# 07_CONNECTORS.net
KiCad netlist of a schematic drawn in Altium Designer
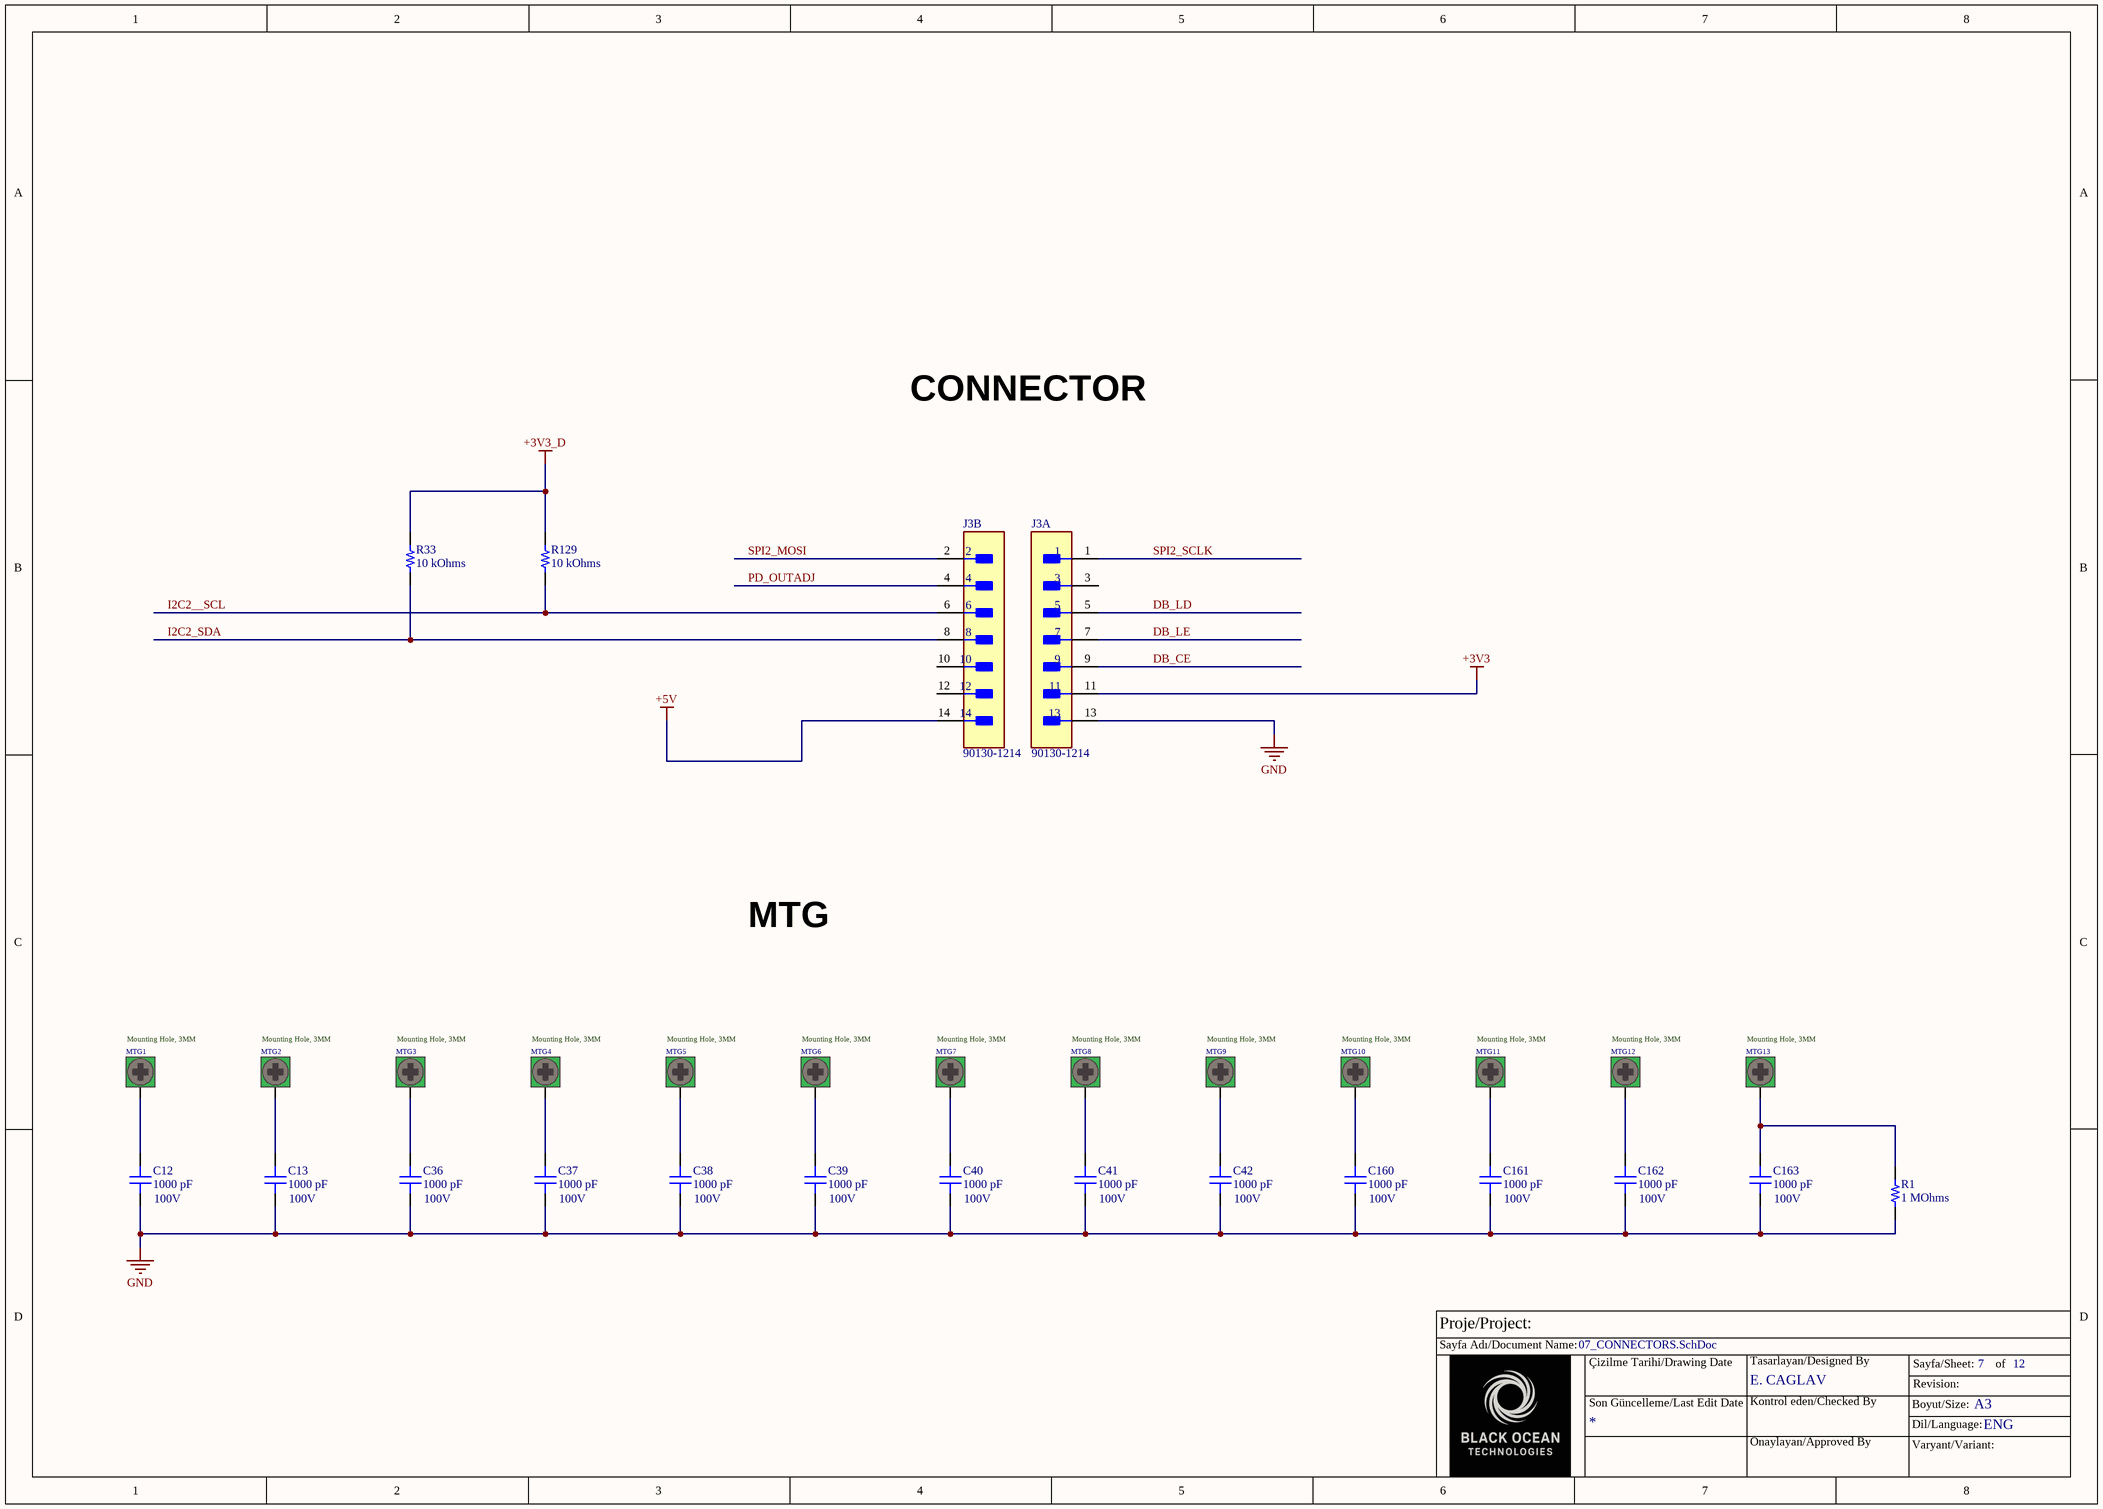
[diagram p0: 07_CONNECTORS.SchDoc]

(export (version "E")
  (design (tool "Eeschema 10.0.6"))
  (components
    (comp (ref "C12")
      (value "1000 pF")
      (footprint "CAP 0402_1005")
      (description "CAP CER 1000PF 100V C0G/NP0 0402")
      (fields
        (field (name "PART NUMBER") "C0402H102J1GAC7867")
        (field (name "CAPACITANCE") "1000 pF")
        (field (name "MANUFACTURER") "KEMET")
        (field (name "VOLTAGE - RATED") "100V")
      )
      (libsource (lib "Celestial Altium Library - altium_library") (part "Capacitor"))
    )
    (comp (ref "C13")
      (value "1000 pF")
      (footprint "CAP 0402_1005")
      (description "CAP CER 1000PF 100V C0G/NP0 0402")
      (fields
        (field (name "PART NUMBER") "C0402H102J1GAC7867")
        (field (name "CAPACITANCE") "1000 pF")
        (field (name "MANUFACTURER") "KEMET")
        (field (name "VOLTAGE - RATED") "100V")
      )
      (libsource (lib "Celestial Altium Library - altium_library") (part "Capacitor"))
    )
    (comp (ref "C36")
      (value "1000 pF")
      (footprint "CAP 0402_1005")
      (description "CAP CER 1000PF 100V C0G/NP0 0402")
      (fields
        (field (name "PART NUMBER") "C0402H102J1GAC7867")
        (field (name "CAPACITANCE") "1000 pF")
        (field (name "MANUFACTURER") "KEMET")
        (field (name "VOLTAGE - RATED") "100V")
      )
      (libsource (lib "Celestial Altium Library - altium_library") (part "Capacitor"))
    )
    (comp (ref "C37")
      (value "1000 pF")
      (footprint "CAP 0402_1005")
      (description "CAP CER 1000PF 100V C0G/NP0 0402")
      (fields
        (field (name "PART NUMBER") "C0402H102J1GAC7867")
        (field (name "CAPACITANCE") "1000 pF")
        (field (name "MANUFACTURER") "KEMET")
        (field (name "VOLTAGE - RATED") "100V")
      )
      (libsource (lib "Celestial Altium Library - altium_library") (part "Capacitor"))
    )
    (comp (ref "C38")
      (value "1000 pF")
      (footprint "CAP 0402_1005")
      (description "CAP CER 1000PF 100V C0G/NP0 0402")
      (fields
        (field (name "PART NUMBER") "C0402H102J1GAC7867")
        (field (name "CAPACITANCE") "1000 pF")
        (field (name "MANUFACTURER") "KEMET")
        (field (name "VOLTAGE - RATED") "100V")
      )
      (libsource (lib "Celestial Altium Library - altium_library") (part "Capacitor"))
    )
    (comp (ref "C39")
      (value "1000 pF")
      (footprint "CAP 0402_1005")
      (description "CAP CER 1000PF 100V C0G/NP0 0402")
      (fields
        (field (name "PART NUMBER") "C0402H102J1GAC7867")
        (field (name "CAPACITANCE") "1000 pF")
        (field (name "MANUFACTURER") "KEMET")
        (field (name "VOLTAGE - RATED") "100V")
      )
      (libsource (lib "Celestial Altium Library - altium_library") (part "Capacitor"))
    )
    (comp (ref "C40")
      (value "1000 pF")
      (footprint "CAP 0402_1005")
      (description "CAP CER 1000PF 100V C0G/NP0 0402")
      (fields
        (field (name "PART NUMBER") "C0402H102J1GAC7867")
        (field (name "CAPACITANCE") "1000 pF")
        (field (name "MANUFACTURER") "KEMET")
        (field (name "VOLTAGE - RATED") "100V")
      )
      (libsource (lib "Celestial Altium Library - altium_library") (part "Capacitor"))
    )
    (comp (ref "C41")
      (value "1000 pF")
      (footprint "CAP 0402_1005")
      (description "CAP CER 1000PF 100V C0G/NP0 0402")
      (fields
        (field (name "PART NUMBER") "C0402H102J1GAC7867")
        (field (name "CAPACITANCE") "1000 pF")
        (field (name "MANUFACTURER") "KEMET")
        (field (name "VOLTAGE - RATED") "100V")
      )
      (libsource (lib "Celestial Altium Library - altium_library") (part "Capacitor"))
    )
    (comp (ref "C42")
      (value "1000 pF")
      (footprint "CAP 0402_1005")
      (description "CAP CER 1000PF 100V C0G/NP0 0402")
      (fields
        (field (name "PART NUMBER") "C0402H102J1GAC7867")
        (field (name "CAPACITANCE") "1000 pF")
        (field (name "MANUFACTURER") "KEMET")
        (field (name "VOLTAGE - RATED") "100V")
      )
      (libsource (lib "Celestial Altium Library - altium_library") (part "Capacitor"))
    )
    (comp (ref "C160")
      (value "1000 pF")
      (footprint "CAP 0402_1005")
      (description "CAP CER 1000PF 100V C0G/NP0 0402")
      (fields
        (field (name "PART NUMBER") "C0402H102J1GAC7867")
        (field (name "CAPACITANCE") "1000 pF")
        (field (name "MANUFACTURER") "KEMET")
        (field (name "VOLTAGE - RATED") "100V")
      )
      (libsource (lib "Celestial Altium Library - altium_library") (part "Capacitor"))
    )
    (comp (ref "C161")
      (value "1000 pF")
      (footprint "CAP 0402_1005")
      (description "CAP CER 1000PF 100V C0G/NP0 0402")
      (fields
        (field (name "PART NUMBER") "C0402H102J1GAC7867")
        (field (name "CAPACITANCE") "1000 pF")
        (field (name "MANUFACTURER") "KEMET")
        (field (name "VOLTAGE - RATED") "100V")
      )
      (libsource (lib "Celestial Altium Library - altium_library") (part "Capacitor"))
    )
    (comp (ref "C162")
      (value "1000 pF")
      (footprint "CAP 0402_1005")
      (description "CAP CER 1000PF 100V C0G/NP0 0402")
      (fields
        (field (name "PART NUMBER") "C0402H102J1GAC7867")
        (field (name "CAPACITANCE") "1000 pF")
        (field (name "MANUFACTURER") "KEMET")
        (field (name "VOLTAGE - RATED") "100V")
      )
      (libsource (lib "Celestial Altium Library - altium_library") (part "Capacitor"))
    )
    (comp (ref "C163")
      (value "1000 pF")
      (footprint "CAP 0402_1005")
      (description "CAP CER 1000PF 100V C0G/NP0 0402")
      (fields
        (field (name "PART NUMBER") "C0402H102J1GAC7867")
        (field (name "CAPACITANCE") "1000 pF")
        (field (name "MANUFACTURER") "KEMET")
        (field (name "VOLTAGE - RATED") "100V")
      )
      (libsource (lib "Celestial Altium Library - altium_library") (part "Capacitor"))
    )
    (comp (ref "J3")
      (value "90130-1214")
      (footprint "FP-90130-1214-MFG")
      (libsource (lib "") (part "7644e1a88aa4da17242a9b8d8257442_1"))
    )
    (comp (ref "MTG1")
      (value "Mounting Hole, 3MM")
      (footprint "MTG-PTH-3MM")
      (libsource (lib "HW_NOMADIQ_2MP_LCD_R1") (part "MTG3MM"))
    )
    (comp (ref "MTG2")
      (value "Mounting Hole, 3MM")
      (footprint "MTG-PTH-3MM")
      (libsource (lib "HW_NOMADIQ_2MP_LCD_R1") (part "MTG3MM"))
    )
    (comp (ref "MTG3")
      (value "Mounting Hole, 3MM")
      (footprint "MTG-PTH-3MM")
      (libsource (lib "HW_NOMADIQ_2MP_LCD_R1") (part "MTG3MM"))
    )
    (comp (ref "MTG4")
      (value "Mounting Hole, 3MM")
      (footprint "MTG-PTH-3MM")
      (libsource (lib "HW_NOMADIQ_2MP_LCD_R1") (part "MTG3MM"))
    )
    (comp (ref "MTG5")
      (value "Mounting Hole, 3MM")
      (footprint "MTG-PTH-3MM")
      (libsource (lib "HW_NOMADIQ_2MP_LCD_R1") (part "MTG3MM"))
    )
    (comp (ref "MTG6")
      (value "Mounting Hole, 3MM")
      (footprint "MTG-PTH-3MM")
      (libsource (lib "HW_NOMADIQ_2MP_LCD_R1") (part "MTG3MM"))
    )
    (comp (ref "MTG7")
      (value "Mounting Hole, 3MM")
      (footprint "MTG-PTH-3MM")
      (libsource (lib "HW_NOMADIQ_2MP_LCD_R1") (part "MTG3MM"))
    )
    (comp (ref "MTG8")
      (value "Mounting Hole, 3MM")
      (footprint "MTG-PTH-3MM")
      (libsource (lib "HW_NOMADIQ_2MP_LCD_R1") (part "MTG3MM"))
    )
    (comp (ref "MTG9")
      (value "Mounting Hole, 3MM")
      (footprint "MTG-PTH-3MM")
      (libsource (lib "HW_NOMADIQ_2MP_LCD_R1") (part "MTG3MM"))
    )
    (comp (ref "MTG10")
      (value "Mounting Hole, 3MM")
      (footprint "MTG-PTH-3MM")
      (libsource (lib "HW_NOMADIQ_2MP_LCD_R1") (part "MTG3MM"))
    )
    (comp (ref "MTG11")
      (value "Mounting Hole, 3MM")
      (footprint "MTG-PTH-3MM")
      (libsource (lib "HW_NOMADIQ_2MP_LCD_R1") (part "MTG3MM"))
    )
    (comp (ref "MTG12")
      (value "Mounting Hole, 3MM")
      (footprint "MTG-PTH-3MM")
      (libsource (lib "HW_NOMADIQ_2MP_LCD_R1") (part "MTG3MM"))
    )
    (comp (ref "MTG13")
      (value "Mounting Hole, 3MM")
      (footprint "MTG-PTH-3MM")
      (libsource (lib "HW_NOMADIQ_2MP_LCD_R1") (part "MTG3MM"))
    )
    (comp (ref "R1")
      (value "1 MOhms")
      (footprint "RES 0402_1005")
      (description "RES SMD 1M OHM 1% 1/16W 0402")
      (fields (field (name "PART NUMBER") "RE0402FRE071ML") (field (name "MANUFACTURER") "Yageo"))
      (libsource (lib "Celestial Altium Library - altium_library") (part "Resistor"))
    )
    (comp (ref "R33")
      (value "10 kOhms")
      (footprint "RES 0402_1005")
      (description "RES 10K OHM 1% 1/16W 0402")
      (fields (field (name "PART NUMBER") "RC0402FR-0710KL") (field (name "MANUFACTURER") "Yageo"))
      (libsource (lib "Celestial Altium Library - altium_library") (part "Resistor"))
    )
    (comp (ref "R129")
      (value "10 kOhms")
      (footprint "RES 0402_1005")
      (description "RES 10K OHM 1% 1/16W 0402")
      (fields (field (name "PART NUMBER") "RC0402FR-0710KL") (field (name "MANUFACTURER") "Yageo"))
      (libsource (lib "Celestial Altium Library - altium_library") (part "Resistor"))
    )
  )
  (nets
    (net (code "1") (name "+3V3") (class "Default")
      (node (ref "J3") (pin "11") (pinfunction "11_11") (pintype "passive"))
    )
    (net (code "2") (name "+3V3_D") (class "Default")
      (node (ref "R129") (pin "1") (pinfunction "1_1") (pintype "passive"))
      (node (ref "R33") (pin "1") (pinfunction "1_1") (pintype "passive"))
    )
    (net (code "3") (name "+5V") (class "Default")
      (node (ref "J3") (pin "14") (pinfunction "14_14") (pintype "passive"))
    )
    (net (code "4") (name "/DB_CE") (class "Default")
      (node (ref "J3") (pin "9") (pinfunction "9_9") (pintype "passive"))
    )
    (net (code "5") (name "/DB_LD") (class "Default")
      (node (ref "J3") (pin "5") (pinfunction "5_5") (pintype "passive"))
    )
    (net (code "6") (name "/DB_LE") (class "Default")
      (node (ref "J3") (pin "7") (pinfunction "7_7") (pintype "passive"))
    )
    (net (code "7") (name "/I2C2_SDA") (class "Default")
      (node (ref "J3") (pin "8") (pinfunction "8_8") (pintype "passive"))
      (node (ref "R33") (pin "2") (pinfunction "2_2") (pintype "passive"))
    )
    (net (code "8") (name "/I2C2__SCL") (class "Default")
      (node (ref "J3") (pin "6") (pinfunction "6_6") (pintype "passive"))
      (node (ref "R129") (pin "2") (pinfunction "2_2") (pintype "passive"))
    )
    (net (code "9") (name "/PD_OUTADJ") (class "Default")
      (node (ref "J3") (pin "4") (pinfunction "4_4") (pintype "passive"))
    )
    (net (code "10") (name "/SPI2_MOSI") (class "Default")
      (node (ref "J3") (pin "2") (pinfunction "2_2") (pintype "passive"))
    )
    (net (code "11") (name "/SPI2_SCLK") (class "Default")
      (node (ref "J3") (pin "1") (pinfunction "1_1") (pintype "passive"))
    )
    (net (code "12") (name "GND") (class "Default")
      (node (ref "C12") (pin "1") (pinfunction "1_1") (pintype "passive"))
      (node (ref "C13") (pin "1") (pinfunction "1_1") (pintype "passive"))
      (node (ref "C160") (pin "1") (pinfunction "1_1") (pintype "passive"))
      (node (ref "C161") (pin "1") (pinfunction "1_1") (pintype "passive"))
      (node (ref "C162") (pin "1") (pinfunction "1_1") (pintype "passive"))
      (node (ref "C163") (pin "1") (pinfunction "1_1") (pintype "passive"))
      (node (ref "C36") (pin "1") (pinfunction "1_1") (pintype "passive"))
      (node (ref "C37") (pin "1") (pinfunction "1_1") (pintype "passive"))
      (node (ref "C38") (pin "1") (pinfunction "1_1") (pintype "passive"))
      (node (ref "C39") (pin "1") (pinfunction "1_1") (pintype "passive"))
      (node (ref "C40") (pin "1") (pinfunction "1_1") (pintype "passive"))
      (node (ref "C41") (pin "1") (pinfunction "1_1") (pintype "passive"))
      (node (ref "C42") (pin "1") (pinfunction "1_1") (pintype "passive"))
      (node (ref "J3") (pin "13") (pinfunction "13_13") (pintype "passive"))
      (node (ref "R1") (pin "1") (pinfunction "1_1") (pintype "passive"))
    )
    (net (code "13") (name "Net-(C12-Pad2)") (class "Default")
      (node (ref "C12") (pin "2") (pinfunction "2_2") (pintype "passive"))
      (node (ref "MTG1") (pin "0") (pinfunction "0_0") (pintype "passive"))
    )
    (net (code "14") (name "Net-(C13-Pad2)") (class "Default")
      (node (ref "C13") (pin "2") (pinfunction "2_2") (pintype "passive"))
      (node (ref "MTG2") (pin "0") (pinfunction "0_0") (pintype "passive"))
    )
    (net (code "15") (name "Net-(C36-Pad2)") (class "Default")
      (node (ref "C36") (pin "2") (pinfunction "2_2") (pintype "passive"))
      (node (ref "MTG3") (pin "0") (pinfunction "0_0") (pintype "passive"))
    )
    (net (code "16") (name "Net-(C37-Pad2)") (class "Default")
      (node (ref "C37") (pin "2") (pinfunction "2_2") (pintype "passive"))
      (node (ref "MTG4") (pin "0") (pinfunction "0_0") (pintype "passive"))
    )
    (net (code "17") (name "Net-(C38-Pad2)") (class "Default")
      (node (ref "C38") (pin "2") (pinfunction "2_2") (pintype "passive"))
      (node (ref "MTG5") (pin "0") (pinfunction "0_0") (pintype "passive"))
    )
    (net (code "18") (name "Net-(C39-Pad2)") (class "Default")
      (node (ref "C39") (pin "2") (pinfunction "2_2") (pintype "passive"))
      (node (ref "MTG6") (pin "0") (pinfunction "0_0") (pintype "passive"))
    )
    (net (code "19") (name "Net-(C40-Pad2)") (class "Default")
      (node (ref "C40") (pin "2") (pinfunction "2_2") (pintype "passive"))
      (node (ref "MTG7") (pin "0") (pinfunction "0_0") (pintype "passive"))
    )
    (net (code "20") (name "Net-(C41-Pad2)") (class "Default")
      (node (ref "C41") (pin "2") (pinfunction "2_2") (pintype "passive"))
      (node (ref "MTG8") (pin "0") (pinfunction "0_0") (pintype "passive"))
    )
    (net (code "21") (name "Net-(C42-Pad2)") (class "Default")
      (node (ref "C42") (pin "2") (pinfunction "2_2") (pintype "passive"))
      (node (ref "MTG9") (pin "0") (pinfunction "0_0") (pintype "passive"))
    )
    (net (code "22") (name "Net-(C160-Pad2)") (class "Default")
      (node (ref "C160") (pin "2") (pinfunction "2_2") (pintype "passive"))
      (node (ref "MTG10") (pin "0") (pinfunction "0_0") (pintype "passive"))
    )
    (net (code "23") (name "Net-(C161-Pad2)") (class "Default")
      (node (ref "C161") (pin "2") (pinfunction "2_2") (pintype "passive"))
      (node (ref "MTG11") (pin "0") (pinfunction "0_0") (pintype "passive"))
    )
    (net (code "24") (name "Net-(C162-Pad2)") (class "Default")
      (node (ref "C162") (pin "2") (pinfunction "2_2") (pintype "passive"))
      (node (ref "MTG12") (pin "0") (pinfunction "0_0") (pintype "passive"))
    )
    (net (code "25") (name "Net-(C163-Pad2)") (class "Default")
      (node (ref "C163") (pin "2") (pinfunction "2_2") (pintype "passive"))
      (node (ref "MTG13") (pin "0") (pinfunction "0_0") (pintype "passive"))
      (node (ref "R1") (pin "2") (pinfunction "2_2") (pintype "passive"))
    )
    (net (code "26") (name "unconnected-(J3-Pad3)") (class "Default")
      (node (ref "J3") (pin "3") (pinfunction "3_3") (pintype "passive"))
    )
    (net (code "27") (name "unconnected-(J3-Pad10)") (class "Default")
      (node (ref "J3") (pin "10") (pinfunction "10_10") (pintype "passive"))
    )
    (net (code "28") (name "unconnected-(J3-Pad12)") (class "Default")
      (node (ref "J3") (pin "12") (pinfunction "12_12") (pintype "passive"))
    )
  )
)
